# 05_-_CONNECTORS.net
KiCad netlist of a schematic drawn in Altium Designer
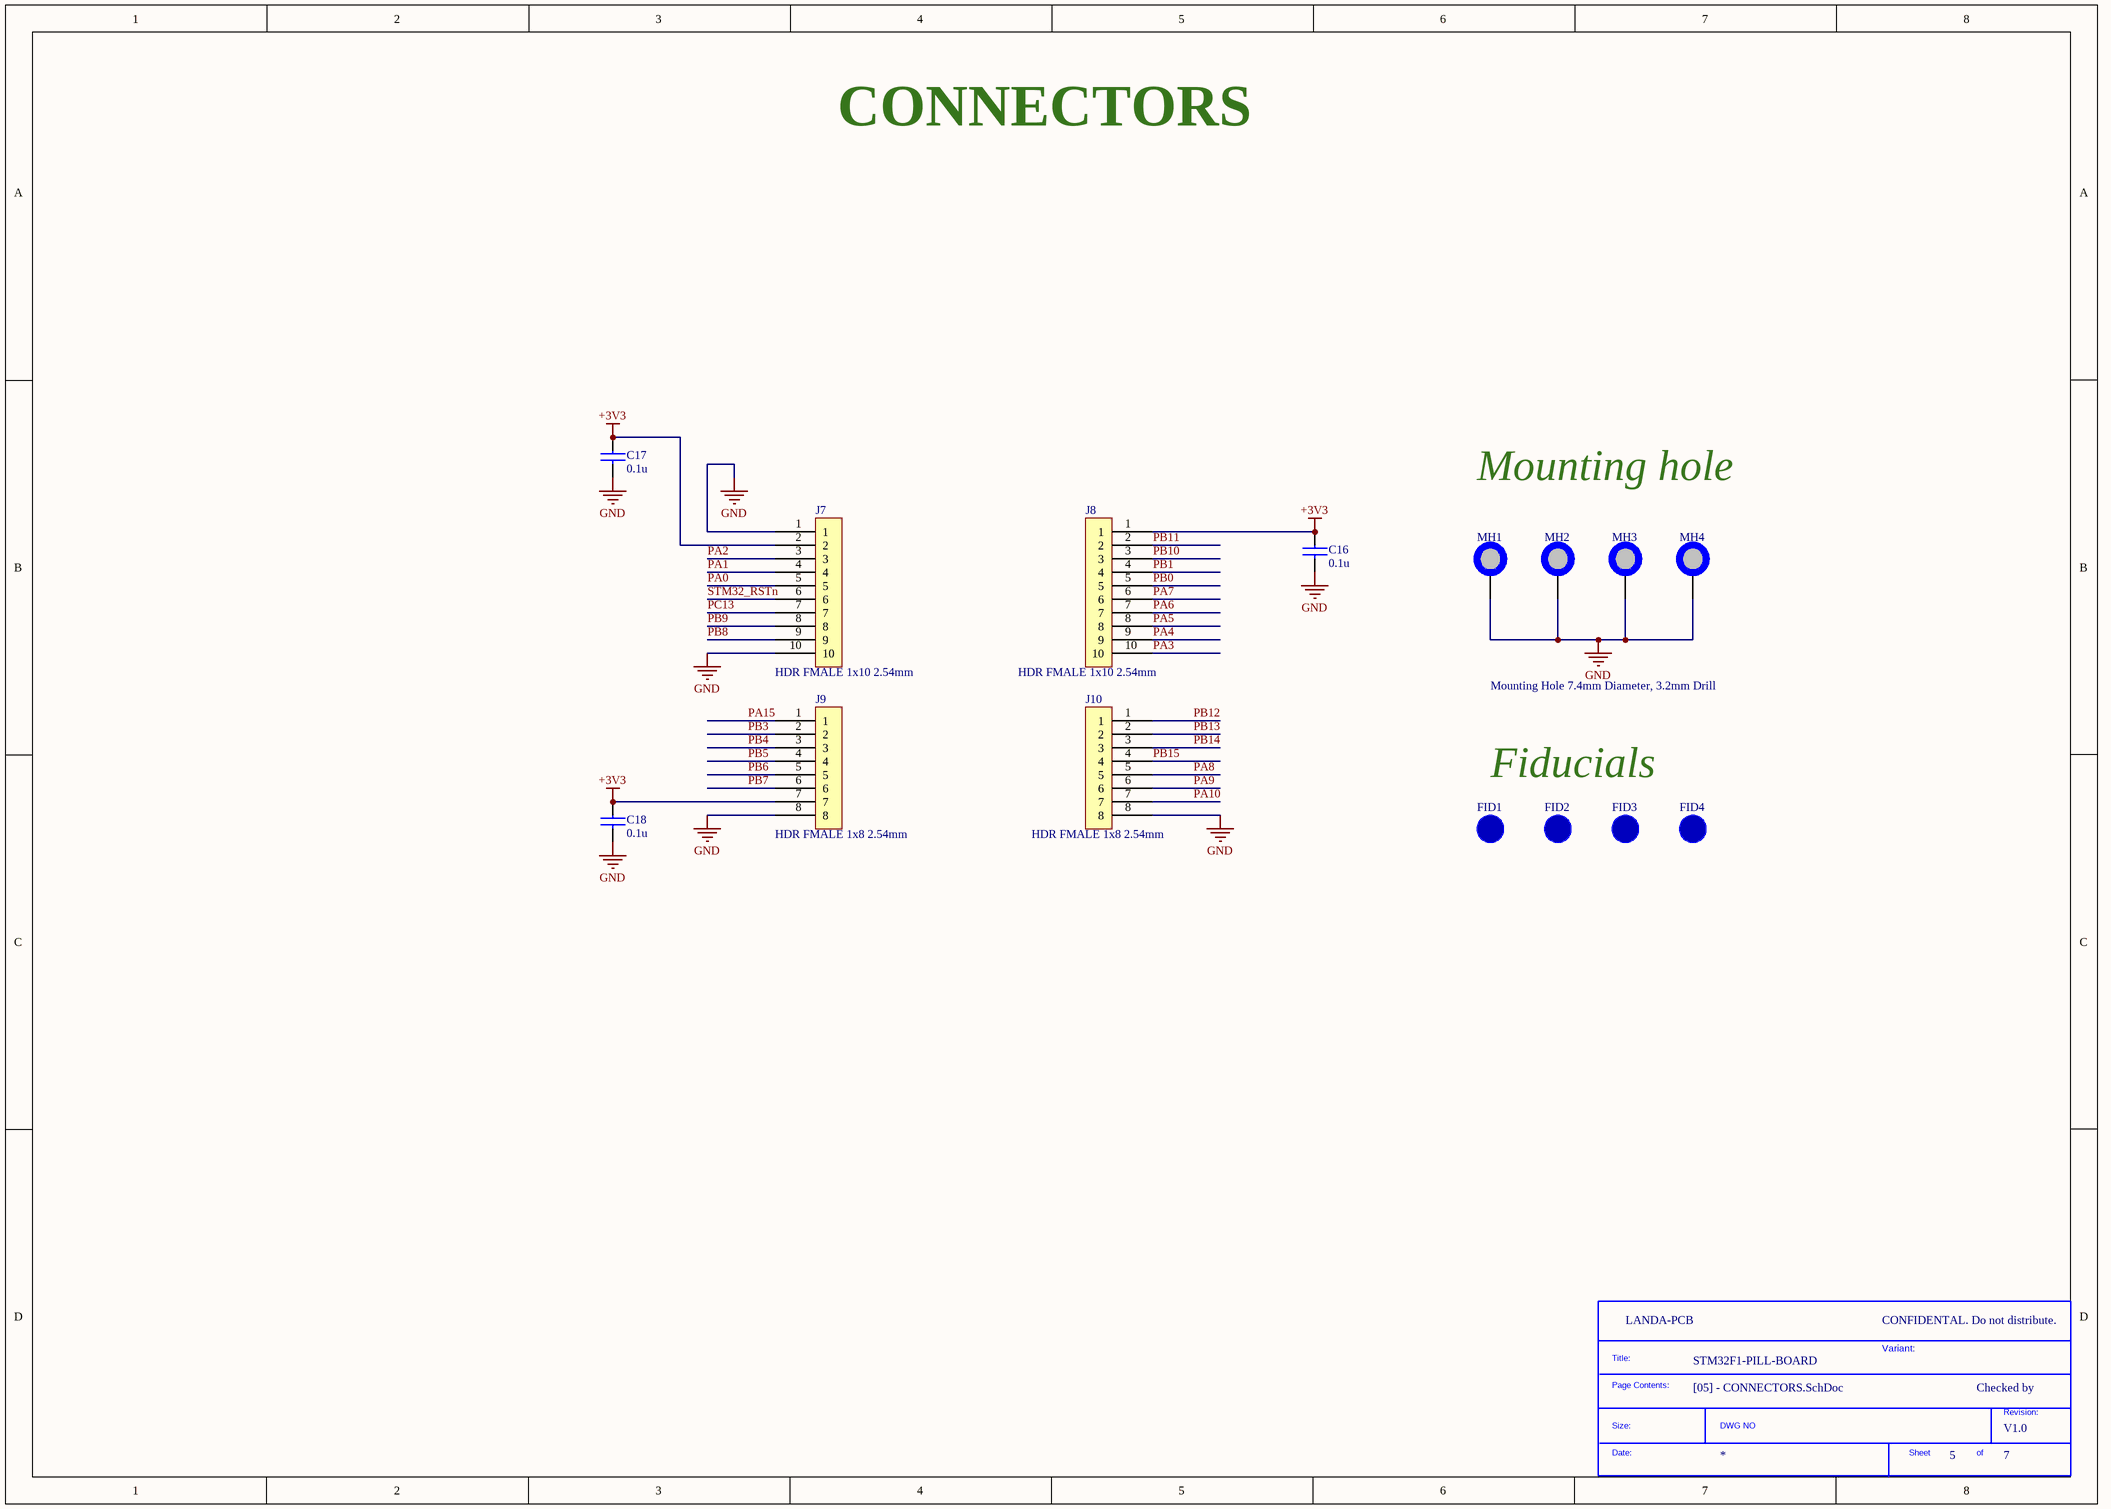
[diagram p0: [05] - CONNECTORS.SchDoc]

(export (version "E")
  (design (tool "Eeschema 10.0.6"))
  (components
    (comp (ref "C16")
      (value "0.1u")
      (footprint "STM32-PILL-PCB:C0805")
      (description "CAP CER 0.1UF 50V 10% X7R 0805")
      (fields
        (field (name "MANUFACTURER") "TDK")
        (field (name "MANUFACTURER PART NUMBER") "C2012X7R1H104K085AA")
      )
      (libsource (lib "STM32-PILL-SHC") (part "C2012X7R1H104K085AA"))
    )
    (comp (ref "C17")
      (value "0.1u")
      (footprint "STM32-PILL-PCB:C0805")
      (description "CAP CER 0.1UF 50V 10% X7R 0805")
      (fields
        (field (name "MANUFACTURER") "TDK")
        (field (name "MANUFACTURER PART NUMBER") "C2012X7R1H104K085AA")
      )
      (libsource (lib "STM32-PILL-SHC") (part "C2012X7R1H104K085AA"))
    )
    (comp (ref "C18")
      (value "0.1u")
      (footprint "STM32-PILL-PCB:C0805")
      (description "CAP CER 0.1UF 50V 10% X7R 0805")
      (fields
        (field (name "MANUFACTURER") "TDK")
        (field (name "MANUFACTURER PART NUMBER") "C2012X7R1H104K085AA")
      )
      (libsource (lib "STM32-PILL-SHC") (part "C2012X7R1H104K085AA"))
    )
    (comp (ref "FID1")
      (value "FID_1MMC")
      (footprint "STM32-PILL-PCB:FID_40X120D")
      (description "Fiducial 40mil Diameter, 120mil Mask")
      (libsource (lib "STM32-PILL-SHC") (part "FID_1MMC"))
    )
    (comp (ref "FID2")
      (value "FID_1MMC")
      (footprint "STM32-PILL-PCB:FID_40X120D")
      (description "Fiducial 40mil Diameter, 120mil Mask")
      (libsource (lib "STM32-PILL-SHC") (part "FID_1MMC"))
    )
    (comp (ref "FID3")
      (value "FID_1MMC")
      (footprint "STM32-PILL-PCB:FID_40X120D")
      (description "Fiducial 40mil Diameter, 120mil Mask")
      (libsource (lib "STM32-PILL-SHC") (part "FID_1MMC"))
    )
    (comp (ref "FID4")
      (value "FID_1MMC")
      (footprint "STM32-PILL-PCB:FID_40X120D")
      (description "Fiducial 40mil Diameter, 120mil Mask")
      (libsource (lib "STM32-PILL-SHC") (part "FID_1MMC"))
    )
    (comp (ref "J7")
      (value "HDR FMALE 1x10 2.54mm")
      (footprint "STM32-PILL-PCB:Hdr_Female_1x10_2.54mm")
      (fields (field (name "MANUFACTURER") "Harwin") (field (name "MANUFACTURER PART NUMBER") "M20-7821046"))
      (libsource (lib "") (part "M20-7821046_1"))
    )
    (comp (ref "J8")
      (value "HDR FMALE 1x10 2.54mm")
      (footprint "STM32-PILL-PCB:Hdr_Female_1x10_2.54mm")
      (fields (field (name "MANUFACTURER") "Harwin") (field (name "MANUFACTURER PART NUMBER") "M20-7821046"))
      (libsource (lib "STM32-PILL-SHC") (part "M20-7821046"))
    )
    (comp (ref "J9")
      (value "HDR FMALE 1x8 2.54mm")
      (footprint "STM32-PILL-PCB:Hdr_Female_1x8_2.54mm")
      (description "08-WAY SIL VERT SOCKET L/FREE")
      (fields (field (name "MANUFACTURER") "Harwin") (field (name "MANUFACTURER PART NUMBER") "M20-7820842"))
      (libsource (lib "") (part "M20-7820842_1"))
    )
    (comp (ref "J10")
      (value "HDR FMALE 1x8 2.54mm")
      (footprint "STM32-PILL-PCB:Hdr_Female_1x8_2.54mm")
      (description "08-WAY SIL VERT SOCKET L/FREE")
      (fields (field (name "MANUFACTURER") "Harwin") (field (name "MANUFACTURER PART NUMBER") "M20-7820842"))
      (libsource (lib "STM32-PILL-SHC") (part "M20-7820842"))
    )
    (comp (ref "MH1")
      (value "Mounting Hole 7.4mm Diameter, 3.2mm Drill")
      (footprint "STM32-PILL-PCB:MH_7.4MMD_3.2MMD")
      (libsource (lib "STM32-PILL-SHC") (part "MH_7.4MMC_3.2MMD"))
    )
    (comp (ref "MH2")
      (value "Mounting Hole 7.4mm Diameter, 3.2mm Drill")
      (footprint "STM32-PILL-PCB:MH_7.4MMD_3.2MMD")
      (libsource (lib "STM32-PILL-SHC") (part "MH_7.4MMC_3.2MMD"))
    )
    (comp (ref "MH3")
      (value "Mounting Hole 7.4mm Diameter, 3.2mm Drill")
      (footprint "STM32-PILL-PCB:MH_7.4MMD_3.2MMD")
      (libsource (lib "STM32-PILL-SHC") (part "MH_7.4MMC_3.2MMD"))
    )
    (comp (ref "MH4")
      (value "Mounting Hole 7.4mm Diameter, 3.2mm Drill")
      (footprint "STM32-PILL-PCB:MH_7.4MMD_3.2MMD")
      (libsource (lib "STM32-PILL-SHC") (part "MH_7.4MMC_3.2MMD"))
    )
  )
  (nets
    (net (code "1") (name "+3V3") (class "Default")
      (node (ref "C16") (pin "1") (pinfunction "1_1") (pintype "passive"))
      (node (ref "C17") (pin "1") (pinfunction "1_1") (pintype "passive"))
      (node (ref "C18") (pin "1") (pinfunction "1_1") (pintype "passive"))
      (node (ref "J7") (pin "2") (pinfunction "2_2") (pintype "passive"))
      (node (ref "J8") (pin "1") (pinfunction "1_1") (pintype "passive"))
      (node (ref "J9") (pin "7") (pinfunction "7_7") (pintype "passive"))
    )
    (net (code "2") (name "/PA0") (class "Default")
      (node (ref "J7") (pin "5") (pinfunction "5_5") (pintype "passive"))
    )
    (net (code "3") (name "/PA1") (class "Default")
      (node (ref "J7") (pin "4") (pinfunction "4_4") (pintype "passive"))
    )
    (net (code "4") (name "/PA2") (class "Default")
      (node (ref "J7") (pin "3") (pinfunction "3_3") (pintype "passive"))
    )
    (net (code "5") (name "/PA3") (class "Default")
      (node (ref "J8") (pin "10") (pinfunction "10_10") (pintype "passive"))
    )
    (net (code "6") (name "/PA4") (class "Default")
      (node (ref "J8") (pin "9") (pinfunction "9_9") (pintype "passive"))
    )
    (net (code "7") (name "/PA5") (class "Default")
      (node (ref "J8") (pin "8") (pinfunction "8_8") (pintype "passive"))
    )
    (net (code "8") (name "/PA6") (class "Default")
      (node (ref "J8") (pin "7") (pinfunction "7_7") (pintype "passive"))
    )
    (net (code "9") (name "/PA7") (class "Default")
      (node (ref "J8") (pin "6") (pinfunction "6_6") (pintype "passive"))
    )
    (net (code "10") (name "/PA8") (class "Default")
      (node (ref "J10") (pin "5") (pinfunction "5_5") (pintype "passive"))
    )
    (net (code "11") (name "/PA9") (class "Default")
      (node (ref "J10") (pin "6") (pinfunction "6_6") (pintype "passive"))
    )
    (net (code "12") (name "/PA10") (class "Default")
      (node (ref "J10") (pin "7") (pinfunction "7_7") (pintype "passive"))
    )
    (net (code "13") (name "/PA15") (class "Default")
      (node (ref "J9") (pin "1") (pinfunction "1_1") (pintype "passive"))
    )
    (net (code "14") (name "/PB0") (class "Default")
      (node (ref "J8") (pin "5") (pinfunction "5_5") (pintype "passive"))
    )
    (net (code "15") (name "/PB1") (class "Default")
      (node (ref "J8") (pin "4") (pinfunction "4_4") (pintype "passive"))
    )
    (net (code "16") (name "/PB3") (class "Default")
      (node (ref "J9") (pin "2") (pinfunction "2_2") (pintype "passive"))
    )
    (net (code "17") (name "/PB4") (class "Default")
      (node (ref "J9") (pin "3") (pinfunction "3_3") (pintype "passive"))
    )
    (net (code "18") (name "/PB5") (class "Default")
      (node (ref "J9") (pin "4") (pinfunction "4_4") (pintype "passive"))
    )
    (net (code "19") (name "/PB6") (class "Default")
      (node (ref "J9") (pin "5") (pinfunction "5_5") (pintype "passive"))
    )
    (net (code "20") (name "/PB7") (class "Default")
      (node (ref "J9") (pin "6") (pinfunction "6_6") (pintype "passive"))
    )
    (net (code "21") (name "/PB8") (class "Default")
      (node (ref "J7") (pin "9") (pinfunction "9_9") (pintype "passive"))
    )
    (net (code "22") (name "/PB9") (class "Default")
      (node (ref "J7") (pin "8") (pinfunction "8_8") (pintype "passive"))
    )
    (net (code "23") (name "/PB10") (class "Default")
      (node (ref "J8") (pin "3") (pinfunction "3_3") (pintype "passive"))
    )
    (net (code "24") (name "/PB11") (class "Default")
      (node (ref "J8") (pin "2") (pinfunction "2_2") (pintype "passive"))
    )
    (net (code "25") (name "/PB12") (class "Default")
      (node (ref "J10") (pin "1") (pinfunction "1_1") (pintype "passive"))
    )
    (net (code "26") (name "/PB13") (class "Default")
      (node (ref "J10") (pin "2") (pinfunction "2_2") (pintype "passive"))
    )
    (net (code "27") (name "/PB14") (class "Default")
      (node (ref "J10") (pin "3") (pinfunction "3_3") (pintype "passive"))
    )
    (net (code "28") (name "/PB15") (class "Default")
      (node (ref "J10") (pin "4") (pinfunction "4_4") (pintype "passive"))
    )
    (net (code "29") (name "/PC13") (class "Default")
      (node (ref "J7") (pin "7") (pinfunction "7_7") (pintype "passive"))
    )
    (net (code "30") (name "/STM32_RSTn") (class "Default")
      (node (ref "J7") (pin "6") (pinfunction "6_6") (pintype "passive"))
    )
    (net (code "31") (name "GND") (class "Default")
      (node (ref "C16") (pin "2") (pinfunction "2_2") (pintype "passive"))
      (node (ref "C17") (pin "2") (pinfunction "2_2") (pintype "passive"))
      (node (ref "C18") (pin "2") (pinfunction "2_2") (pintype "passive"))
      (node (ref "J10") (pin "8") (pinfunction "8_8") (pintype "passive"))
      (node (ref "J7") (pin "1") (pinfunction "1_1") (pintype "passive"))
      (node (ref "J7") (pin "10") (pinfunction "10_10") (pintype "passive"))
      (node (ref "J9") (pin "8") (pinfunction "8_8") (pintype "passive"))
      (node (ref "MH1") (pin "1") (pinfunction "1_1") (pintype "passive"))
      (node (ref "MH2") (pin "1") (pinfunction "1_1") (pintype "passive"))
      (node (ref "MH3") (pin "1") (pinfunction "1_1") (pintype "passive"))
      (node (ref "MH4") (pin "1") (pinfunction "1_1") (pintype "passive"))
    )
  )
)
